# Power.net
KiCad netlist of a schematic drawn in Altium Designer
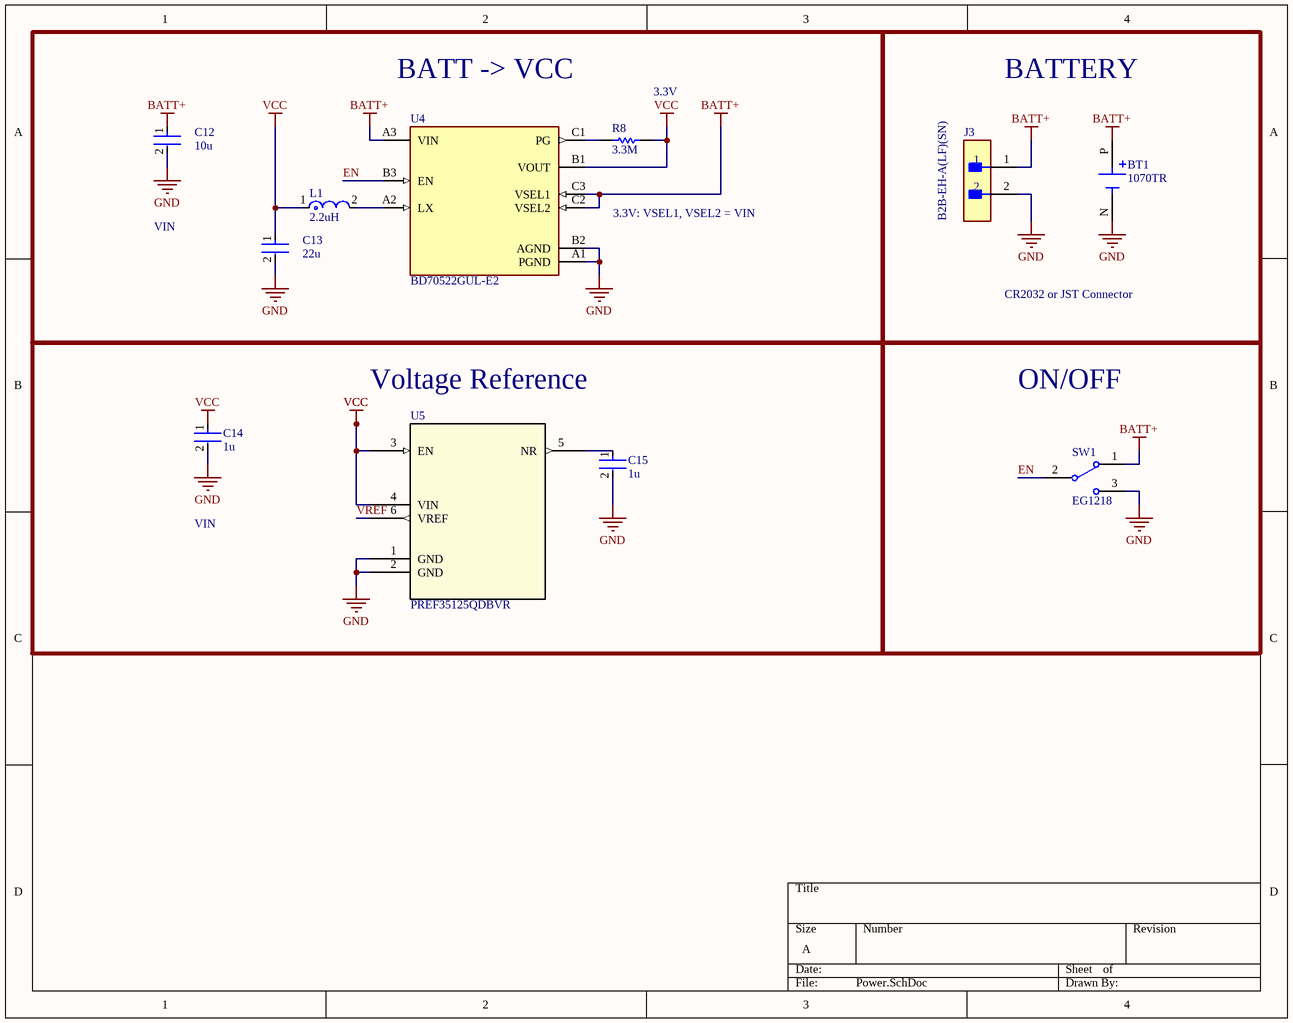
[diagram p0: Power.SchDoc]

(export (version "E")
  (design (tool "Eeschema 10.0.6"))
  (components
    (comp (ref "BT1")
      (value "1070TR")
      (footprint "KEYSTONE_1070TR")
      (libsource (lib "1070TR") (part "1070TR"))
    )
    (comp (ref "C12")
      (value "10u")
      (footprint "FP-GCM31C-0_2-e0_3_0_8-IPC_A")
      (description "Ceramic Capacitor for Automotive 10uF ±10% 16VDC X7R 1206 Embossed T/R")
      (fields (field (name "TOLERANCE") "10%"))
      (libsource (lib "Altium Content Vault") (part "11868f565c42a9108669ba33697ecf6"))
    )
    (comp (ref "C13")
      (value "22u")
      (footprint "FP-GRM32E-0_3-0_2-IPC_B")
      (description "Chip Multilayer Ceramic Capacitors for General Purpose, 1210, 22uF, X7R, 15%, 10%, 16V")
      (fields (field (name "TOLERANCE") "10%") (field (name "VOLTAGE") "16V"))
      (libsource (lib "Altium Content Vault") (part "02cd4be3c70576c341d710602a673aa"))
    )
    (comp (ref "C14")
      (value "1u")
      (footprint "FP-GCM188-0_1-IPC_B")
      (description "Ceramic Capacitor for Automotive 1uF  ±10% 16VDC X7R 0603 Paper T/R")
      (fields (field (name "VOLTAGE") "16V") (field (name "TOLERANCE") "10%"))
      (libsource (lib "Altium Content Vault") (part "02cd4be3c70576c341d710602a673aa"))
    )
    (comp (ref "C15")
      (value "1u")
      (footprint "FP-GCM188-0_1-IPC_B")
      (description "Ceramic Capacitor for Automotive 1uF  ±10% 16VDC X7R 0603 Paper T/R")
      (fields (field (name "VOLTAGE") "16V") (field (name "TOLERANCE") "10%"))
      (libsource (lib "Altium Content Vault") (part "02cd4be3c70576c341d710602a673aa"))
    )
    (comp (ref "J3")
      (value "B2B-EH-A(LF)(SN)")
      (footprint "FP-B2B-EH-A_LF_SN-MFG")
      (description "CONN HEADER VERT 2POS 2.5MM")
      (libsource (lib "Altium Content Vault") (part "3bc925449376181038e59eaffc5286c"))
    )
    (comp (ref "L1")
      (value "2.2uH")
      (footprint "FP-DG6050C-MFG")
      (description "FIXED IND 2.2UH 7.8A 19.2 MOHM")
      (fields (field (name "TOLERANCE") "30%"))
      (libsource (lib "Altium Content Vault") (part "4cc4b267dca4c8e51f7102f422741d8"))
    )
    (comp (ref "R8")
      (value "3.3M")
      (footprint "RESC1005X40X25NL05T10")
      (fields (field (name "MANUFACTURER") "Yageo / Phycomp") (field (name "PART NUMBER") "RC0402FR-073M3L"))
      (libsource (lib "Altium Content Vault") (part "RES"))
    )
    (comp (ref "SW1")
      (value "EG1218")
      (footprint "ESWI-EG1218_V")
      (description "Slide Switch, 500 V, -20 to 70 degC, 3-Pin THD, RoHS")
      (libsource (lib "Altium Content Vault") (part "SW-SPDT-3_B"))
    )
    (comp (ref "U4")
      (value "BD70522GUL-E2")
      (footprint "FP-VCSP50L1C-IPC_C")
      (description "IC REG BUCK ADJ 500MA VCSP50L1")
      (fields
        (field (name "OCTOPART") "https://octopart.com/bd70522gul-e2-rohm-88248999")
        (field (name "MANUFACTURER") "Rohm")
      )
      (libsource (lib "Altium Content Vault") (part "08bf5763a0393711f78ecab715b3c36"))
    )
    (comp (ref "U5")
      (value "PREF35125QDBVR")
      (footprint "SOT23_DBV_TEX")
      (description "650-nA quiescent current, 12-ppm/°C drift, ultra-low-power precision voltage reference")
      (libsource (lib "PREF35125QDBVR") (part "PREF35125QDBVR"))
    )
  )
  (nets
    (net (code "1") (name "/EN") (class "Default")
      (node (ref "SW1") (pin "2") (pinfunction "COM_2") (pintype "passive"))
      (node (ref "U4") (pin "B3") (pinfunction "EN_B3") (pintype "input"))
    )
    (net (code "2") (name "/VREF") (class "Default")
      (node (ref "U5") (pin "6") (pinfunction "VREF_6") (pintype "output"))
    )
    (net (code "3") (name "BATT+") (class "Default")
      (node (ref "BT1") (pin "P") (pinfunction "POS_P") (pintype "passive"))
      (node (ref "C12") (pin "1") (pinfunction "1_1") (pintype "passive"))
      (node (ref "J3") (pin "1") (pinfunction "1_1") (pintype "passive"))
      (node (ref "SW1") (pin "1") (pinfunction "1_1") (pintype "passive"))
      (node (ref "U4") (pin "A3") (pinfunction "VIN_A3") (pintype "power_in"))
      (node (ref "U4") (pin "C2") (pinfunction "VSEL2_C2") (pintype "input"))
      (node (ref "U4") (pin "C3") (pinfunction "VSEL1_C3") (pintype "input"))
    )
    (net (code "4") (name "GND") (class "Default")
      (node (ref "BT1") (pin "N") (pinfunction "NEG_N") (pintype "passive"))
      (node (ref "C12") (pin "2") (pinfunction "2_2") (pintype "passive"))
      (node (ref "C13") (pin "2") (pinfunction "2_2") (pintype "passive"))
      (node (ref "C14") (pin "2") (pinfunction "2_2") (pintype "passive"))
      (node (ref "C15") (pin "2") (pinfunction "2_2") (pintype "passive"))
      (node (ref "J3") (pin "2") (pinfunction "2_2") (pintype "passive"))
      (node (ref "SW1") (pin "3") (pinfunction "3_3") (pintype "passive"))
      (node (ref "U4") (pin "A1") (pinfunction "PGND_A1") (pintype "power_in"))
      (node (ref "U4") (pin "B2") (pinfunction "AGND_B2") (pintype "power_in"))
      (node (ref "U5") (pin "1") (pinfunction "GND_1") (pintype "power_in"))
      (node (ref "U5") (pin "2") (pinfunction "GND_2") (pintype "power_in"))
    )
    (net (code "5") (name "Net-(U4-LX)") (class "Default")
      (node (ref "L1") (pin "2") (pinfunction "2_2") (pintype "passive"))
      (node (ref "U4") (pin "A2") (pinfunction "LX_A2") (pintype "input"))
    )
    (net (code "6") (name "Net-(U4-PG)") (class "Default")
      (node (ref "R8") (pin "1") (pinfunction "1_1") (pintype "passive"))
      (node (ref "U4") (pin "C1") (pinfunction "PG_C1") (pintype "output"))
    )
    (net (code "7") (name "Net-(U5-NR)") (class "Default")
      (node (ref "C15") (pin "1") (pinfunction "1_1") (pintype "passive"))
      (node (ref "U5") (pin "5") (pinfunction "NR_5") (pintype "output"))
    )
    (net (code "8") (name "VCC") (class "Default")
      (node (ref "C13") (pin "1") (pinfunction "1_1") (pintype "passive"))
      (node (ref "C14") (pin "1") (pinfunction "1_1") (pintype "passive"))
      (node (ref "L1") (pin "1") (pinfunction "1_1") (pintype "passive"))
      (node (ref "R8") (pin "2") (pinfunction "2_2") (pintype "passive"))
      (node (ref "U4") (pin "B1") (pinfunction "VOUT_B1") (pintype "power_in"))
      (node (ref "U5") (pin "3") (pinfunction "EN_3") (pintype "input"))
      (node (ref "U5") (pin "4") (pinfunction "VIN_4") (pintype "power_in"))
    )
  )
)
